# S-SSHI.net
KiCad netlist of a schematic drawn in Altium Designer
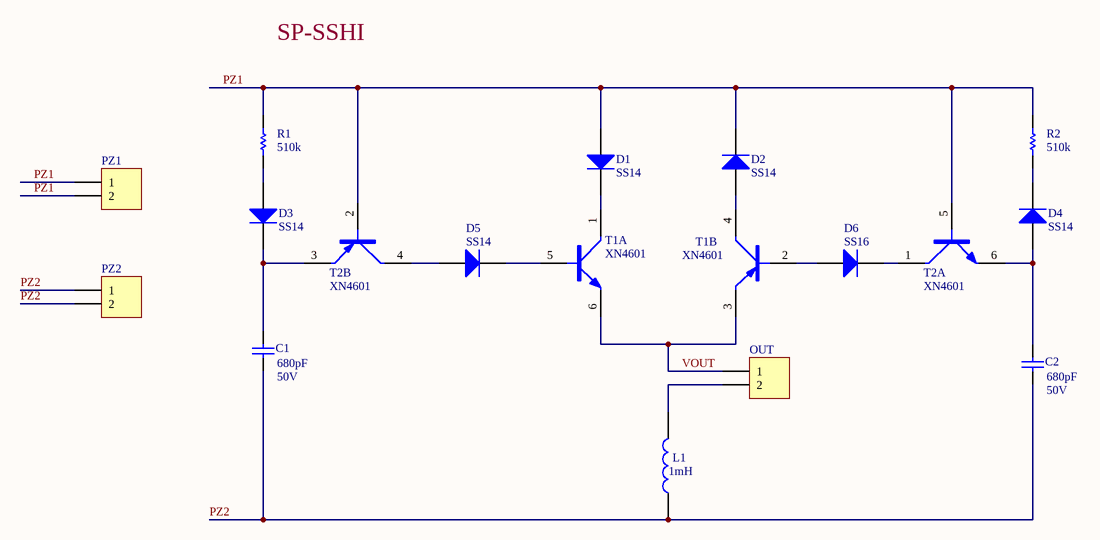
[diagram p0: S-SSHI.SchDoc]

(export (version "E")
  (design (tool "Eeschema 10.0.6"))
  (components
    (comp (ref "C1")
      (value "680pF")
      (footprint "6-0805_N")
      (description "Capacitor")
      (fields
        (field (name "NOMINAL VOLTAGE") "50V")
        (field (name "Comment") "CAP")
        (field (name "PUBLISHER") "Altium Limited")
      )
      (libsource (lib "Harry_PCBLib") (part "Cap"))
    )
    (comp (ref "C2")
      (value "680pF")
      (footprint "6-0805_N")
      (description "Capacitor")
      (fields
        (field (name "NOMINAL VOLTAGE") "50V")
        (field (name "Comment") "CAP")
        (field (name "PUBLISHER") "Altium Limited")
      )
      (libsource (lib "Harry_PCBLib") (part "Cap"))
    )
    (comp (ref "D1")
      (value "SS14")
      (footprint "SMD SS16")
      (description "1 Amp General Purpose Rectifier")
      (fields (field (name "PUBLISHER") "Altium Limited"))
      (libsource (lib "Miscellaneous Devices") (part "Diode 1N4004"))
    )
    (comp (ref "D2")
      (value "SS14")
      (footprint "SMD SS16")
      (description "1 Amp General Purpose Rectifier")
      (fields (field (name "PUBLISHER") "Altium Limited"))
      (libsource (lib "Miscellaneous Devices") (part "Diode 1N4004"))
    )
    (comp (ref "D3")
      (value "SS14")
      (footprint "SMD SS16")
      (description "1 Amp General Purpose Rectifier")
      (fields (field (name "PUBLISHER") "Altium Limited"))
      (libsource (lib "Miscellaneous Devices") (part "Diode 1N4004"))
    )
    (comp (ref "D4")
      (value "SS14")
      (footprint "SMD SS16")
      (description "1 Amp General Purpose Rectifier")
      (fields (field (name "PUBLISHER") "Altium Limited"))
      (libsource (lib "Miscellaneous Devices") (part "Diode 1N4004"))
    )
    (comp (ref "D5")
      (value "SS14")
      (footprint "SMD SS16")
      (description "1 Amp General Purpose Rectifier")
      (fields (field (name "PUBLISHER") "Altium Limited"))
      (libsource (lib "Miscellaneous Devices") (part "Diode 1N4004"))
    )
    (comp (ref "D6")
      (value "SS16")
      (footprint "SMD SS16")
      (description "1 Amp General Purpose Rectifier")
      (fields (field (name "PUBLISHER") "Altium Limited"))
      (libsource (lib "Miscellaneous Devices") (part "Diode 1N4004"))
    )
    (comp (ref "L1") (value "1mH") (footprint "1812") (libsource (lib "Harry_PCBLib") (part "INDUCTOR")))
    (comp (ref "OUT")
      (value "Header 2")
      (footprint "HDR1X2")
      (description "Header, 2-Pin")
      (fields (field (name "PUBLISHER") "Altium Limited"))
      (libsource (lib "Miscellaneous Connectors") (part "Header 2"))
    )
    (comp (ref "PZ1")
      (value "Header 2")
      (footprint "HDR1X2")
      (description "Header, 2-Pin")
      (fields (field (name "PUBLISHER") "Altium Limited"))
      (libsource (lib "Miscellaneous Connectors") (part "Header 2"))
    )
    (comp (ref "PZ2")
      (value "Header 2")
      (footprint "HDR1X2")
      (description "Header, 2-Pin")
      (fields (field (name "PUBLISHER") "Altium Limited"))
      (libsource (lib "Miscellaneous Connectors") (part "Header 2"))
    )
    (comp (ref "R1")
      (value "510k")
      (footprint "6-0805_N")
      (description "Resistor")
      (fields (field (name "Comment") "Res1") (field (name "PUBLISHER") "Altium Limited"))
      (libsource (lib "Miscellaneous Devices") (part "Res1"))
    )
    (comp (ref "R2")
      (value "510k")
      (footprint "6-0805_N")
      (description "Resistor")
      (fields (field (name "Comment") "Res1") (field (name "PUBLISHER") "Altium Limited"))
      (libsource (lib "Miscellaneous Devices") (part "Res1"))
    )
    (comp (ref "T1")
      (value "XN4601")
      (footprint "XN4601")
      (description "Composite Transistors")
      (libsource (lib "Self-power SSHI") (part "XN4601"))
    )
    (comp (ref "T2")
      (value "XN4601")
      (footprint "XN4601")
      (description "Composite Transistors")
      (libsource (lib "Self-power SSHI") (part "XN4601"))
    )
  )
  (nets
    (net (code "1") (name "/PZ1") (class "Default")
      (node (ref "D1") (pin "1") (pinfunction "A_1") (pintype "passive"))
      (node (ref "D2") (pin "2") (pinfunction "K_2") (pintype "passive"))
      (node (ref "PZ1") (pin "1") (pinfunction "1_1") (pintype "passive"))
      (node (ref "PZ1") (pin "2") (pinfunction "2_2") (pintype "passive"))
      (node (ref "R1") (pin "2") (pinfunction "2_2") (pintype "passive"))
      (node (ref "R2") (pin "2") (pinfunction "2_2") (pintype "passive"))
      (node (ref "T2") (pin "2") (pinfunction "PNP_B_2") (pintype "passive"))
      (node (ref "T2") (pin "5") (pinfunction "NPN_B_5") (pintype "passive"))
    )
    (net (code "2") (name "/PZ2") (class "Default")
      (node (ref "C1") (pin "1") (pinfunction "1_1") (pintype "passive"))
      (node (ref "C2") (pin "1") (pinfunction "1_1") (pintype "passive"))
      (node (ref "L1") (pin "1") (pinfunction "1_1") (pintype "passive"))
      (node (ref "PZ2") (pin "1") (pinfunction "1_1") (pintype "passive"))
      (node (ref "PZ2") (pin "2") (pinfunction "2_2") (pintype "passive"))
    )
    (net (code "3") (name "/VOUT") (class "Default")
      (node (ref "OUT") (pin "1") (pinfunction "1_1") (pintype "passive"))
      (node (ref "T1") (pin "3") (pinfunction "PNP_E_3") (pintype "passive"))
      (node (ref "T1") (pin "6") (pinfunction "NPN_E_6") (pintype "passive"))
    )
    (net (code "4") (name "Net-(D1-K)") (class "Default")
      (node (ref "D1") (pin "2") (pinfunction "K_2") (pintype "passive"))
      (node (ref "T1") (pin "1") (pinfunction "NPN_C_1") (pintype "passive"))
    )
    (net (code "5") (name "Net-(D2-A)") (class "Default")
      (node (ref "D2") (pin "1") (pinfunction "A_1") (pintype "passive"))
      (node (ref "T1") (pin "4") (pinfunction "PNP_C_4") (pintype "passive"))
    )
    (net (code "6") (name "Net-(D3-A)") (class "Default")
      (node (ref "D3") (pin "1") (pinfunction "A_1") (pintype "passive"))
      (node (ref "R1") (pin "1") (pinfunction "1_1") (pintype "passive"))
    )
    (net (code "7") (name "Net-(D3-K)") (class "Default")
      (node (ref "C1") (pin "2") (pinfunction "2_2") (pintype "passive"))
      (node (ref "D3") (pin "2") (pinfunction "K_2") (pintype "passive"))
      (node (ref "T2") (pin "3") (pinfunction "PNP_E_3") (pintype "passive"))
    )
    (net (code "8") (name "Net-(D4-A)") (class "Default")
      (node (ref "C2") (pin "2") (pinfunction "2_2") (pintype "passive"))
      (node (ref "D4") (pin "1") (pinfunction "A_1") (pintype "passive"))
      (node (ref "T2") (pin "6") (pinfunction "NPN_E_6") (pintype "passive"))
    )
    (net (code "9") (name "Net-(D4-K)") (class "Default")
      (node (ref "D4") (pin "2") (pinfunction "K_2") (pintype "passive"))
      (node (ref "R2") (pin "1") (pinfunction "1_1") (pintype "passive"))
    )
    (net (code "10") (name "Net-(D5-A)") (class "Default")
      (node (ref "D5") (pin "1") (pinfunction "A_1") (pintype "passive"))
      (node (ref "T2") (pin "4") (pinfunction "PNP_C_4") (pintype "passive"))
    )
    (net (code "11") (name "Net-(D5-K)") (class "Default")
      (node (ref "D5") (pin "2") (pinfunction "K_2") (pintype "passive"))
      (node (ref "T1") (pin "5") (pinfunction "NPN_B_5") (pintype "passive"))
    )
    (net (code "12") (name "Net-(D6-A)") (class "Default")
      (node (ref "D6") (pin "1") (pinfunction "A_1") (pintype "passive"))
      (node (ref "T1") (pin "2") (pinfunction "PNP_B_2") (pintype "passive"))
    )
    (net (code "13") (name "Net-(D6-K)") (class "Default")
      (node (ref "D6") (pin "2") (pinfunction "K_2") (pintype "passive"))
      (node (ref "T2") (pin "1") (pinfunction "NPN_C_1") (pintype "passive"))
    )
    (net (code "14") (name "Net-(L1-Pad2)") (class "Default")
      (node (ref "L1") (pin "2") (pinfunction "2_2") (pintype "passive"))
      (node (ref "OUT") (pin "2") (pinfunction "2_2") (pintype "passive"))
    )
  )
)
